# PCB_project_2020-06-05_12-44-14.net
KiCad netlist of a schematic drawn in EasyEDA
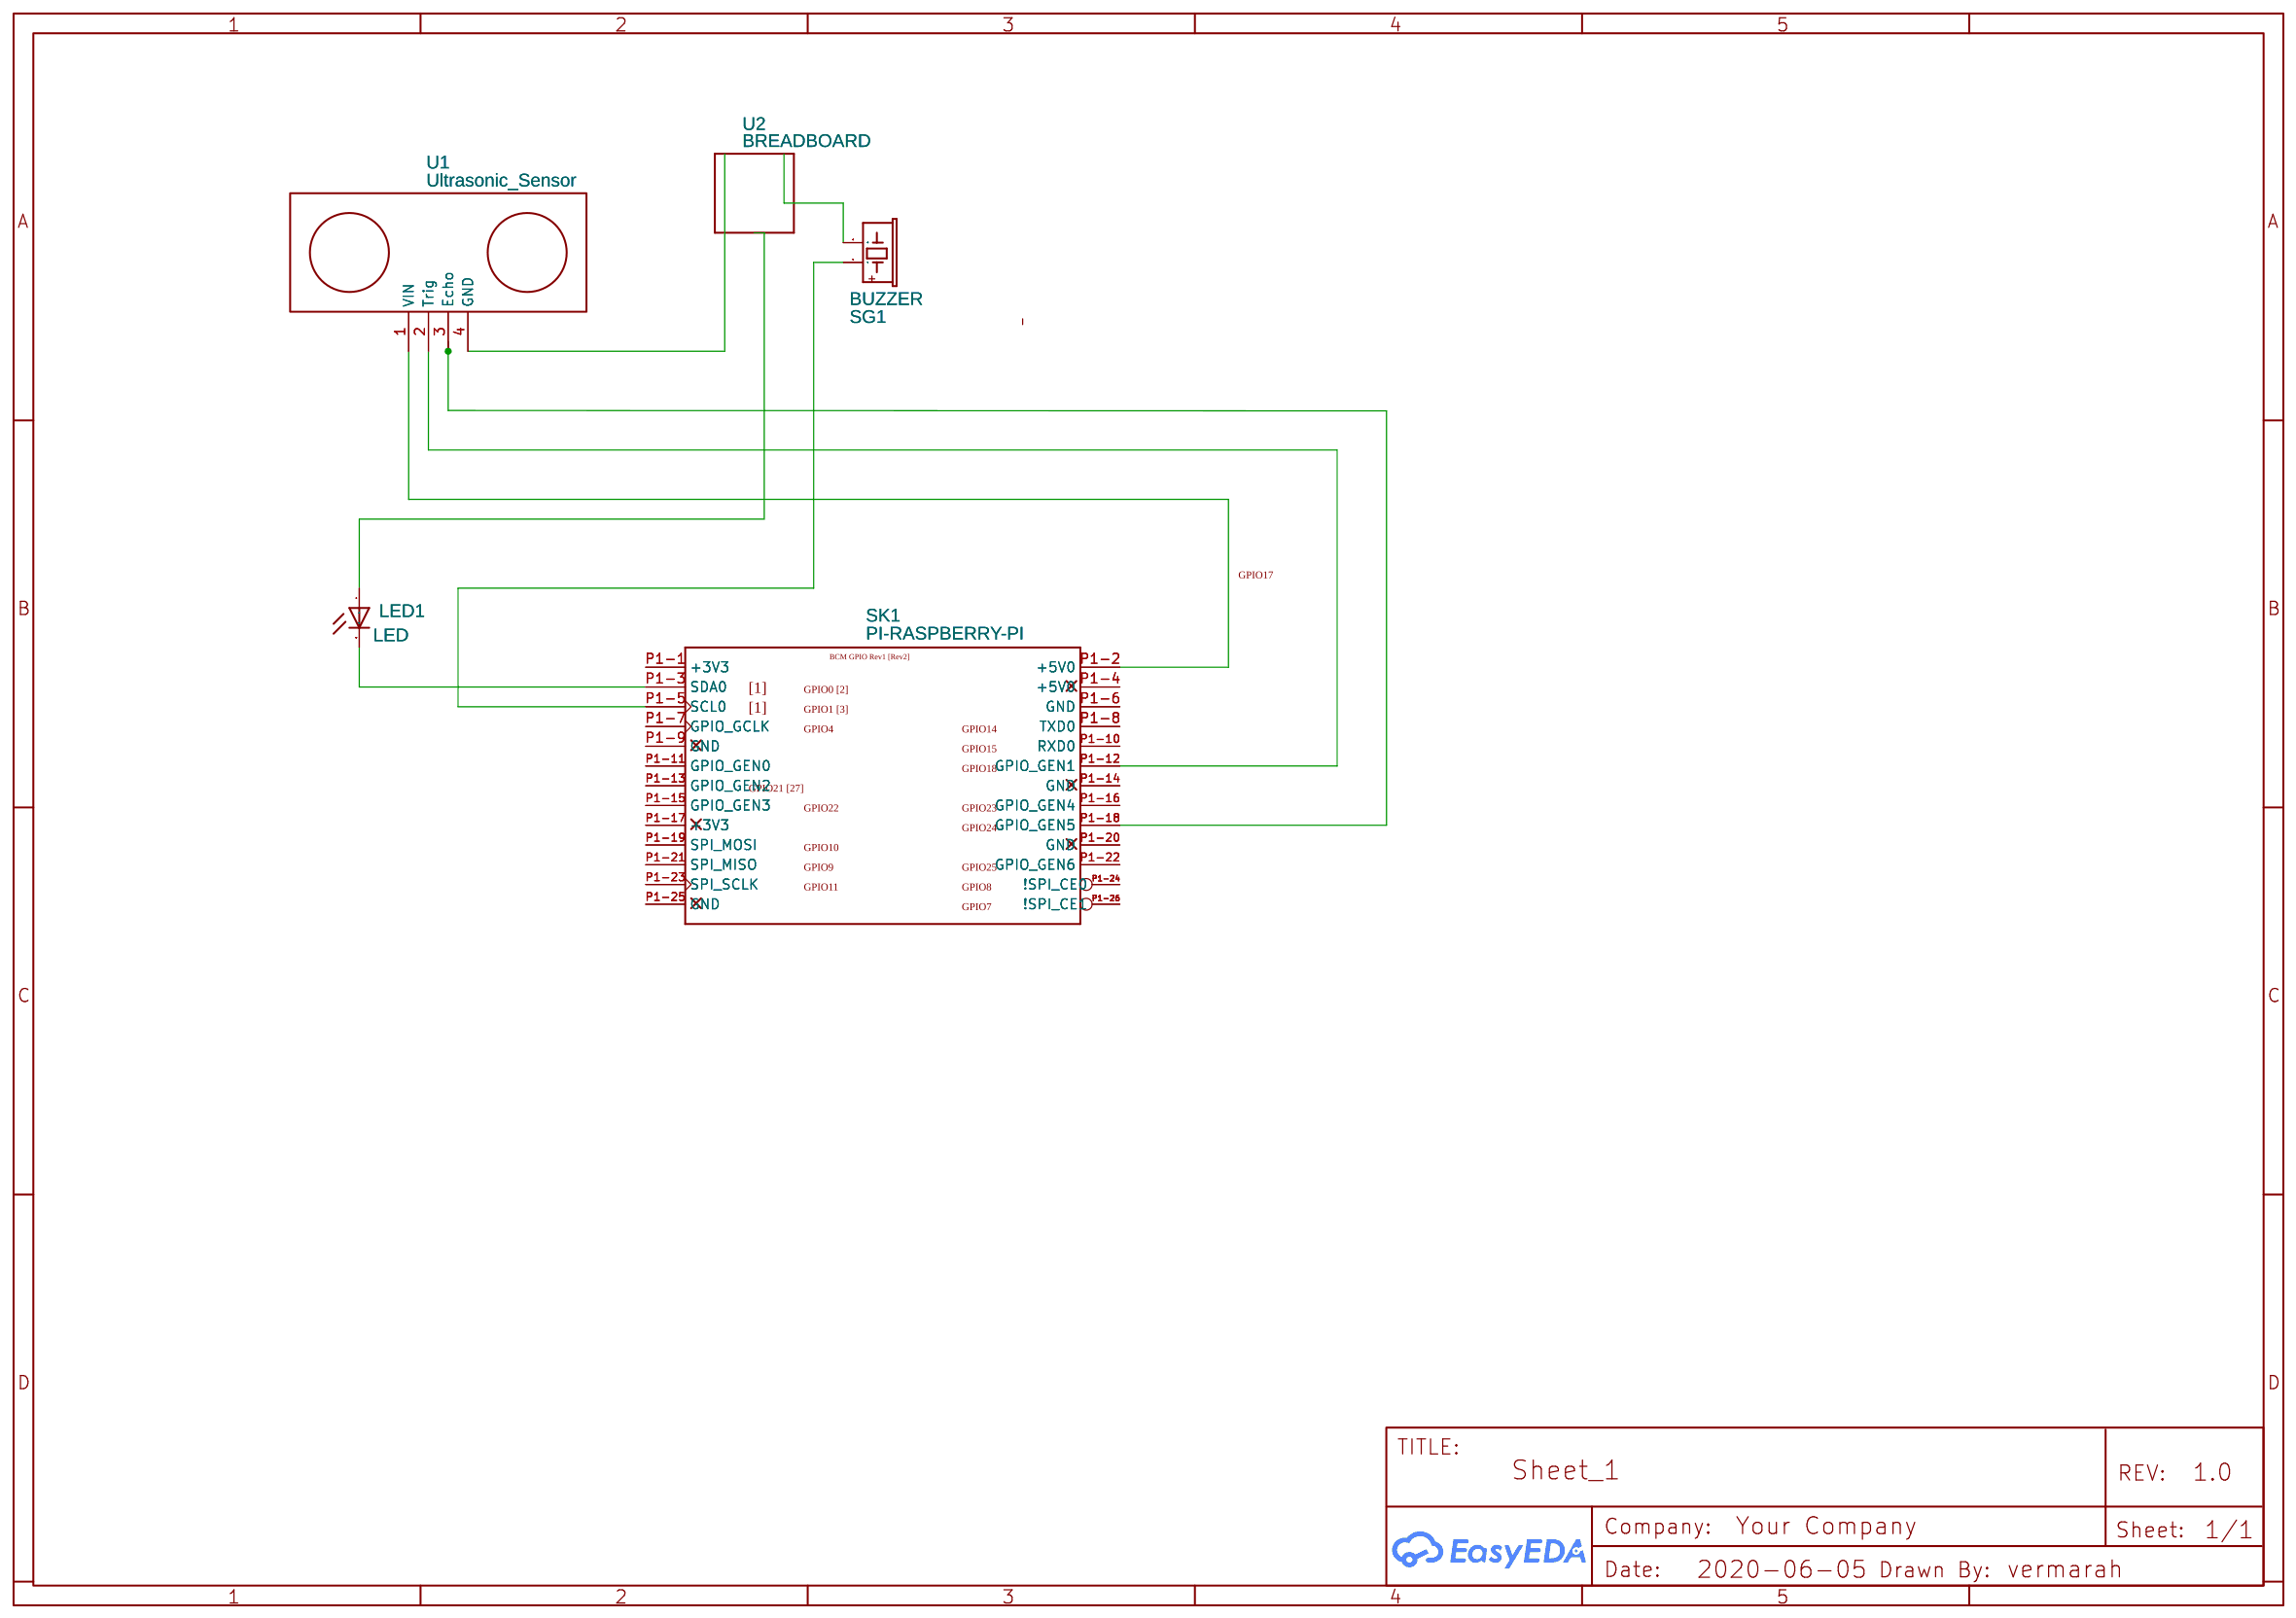
[diagram p0: schematic sheet]

(export (version "E")
  (design (tool "Eeschema 10.0.6"))
  (components
    (comp (ref "LED1") (value "LED") (libsource (lib "") (part "LED")))
    (comp (ref "SG1") (value "BUZZER") (libsource (lib "") (part "BUZZER")))
    (comp (ref "SK1") (value "PI-RASPBERRY-PI") (libsource (lib "") (part "PI-RASPBERRY-PI")))
    (comp (ref "U1")
      (value "Ultrasonic_Sensor")
      (fields (field (name "BOM_Manufacturer Part") "New SchematicLib"))
      (libsource (lib "") (part "Ultrasonic_Sensor"))
    )
    (comp (ref "U2") (value "BREADBOARD") (libsource (lib "") (part "BREADBOARD")))
  )
  (nets
    (net (code "1") (name "Net-(SK1-GPIO_GEN1)") (class "Default")
      (node (ref "SK1") (pin "P1-12") (pinfunction "GPIO_GEN1_P1-12") (pintype "unspecified"))
      (node (ref "U1") (pin "2") (pinfunction "Trig_2") (pintype "unspecified"))
    )
    (net (code "2") (name "Net-(SK1-GPIO_GEN5)") (class "Default")
      (node (ref "SK1") (pin "P1-18") (pinfunction "GPIO_GEN5_P1-18") (pintype "unspecified"))
      (node (ref "U1") (pin "3") (pinfunction "Echo_3") (pintype "unspecified"))
    )
    (net (code "3") (name "Net-(SK1-SCL0)") (class "Default")
      (node (ref "SG1") (pin "1") (pinfunction "1_1") (pintype "unspecified"))
      (node (ref "SK1") (pin "P1-5") (pinfunction "SCL0_P1-5") (pintype "unspecified"))
    )
    (net (code "4") (name "Net-(SK1-SDA0)") (class "Default")
      (node (ref "LED1") (pin "C") (pinfunction "C_C") (pintype "unspecified"))
      (node (ref "SK1") (pin "P1-3") (pinfunction "SDA0_P1-3") (pintype "unspecified"))
    )
    (net (code "5") (name "Net-(U1-VIN)") (class "Default")
      (node (ref "SK1") (pin "P1-2") (pinfunction "+5V0_P1-2") (pintype "passive"))
      (node (ref "U1") (pin "1") (pinfunction "VIN_1") (pintype "unspecified"))
    )
    (net (code "6") (name "unconnected-(LED1-PadA)") (class "Default")
      (node (ref "LED1") (pin "A") (pinfunction "A_A") (pintype "unspecified"))
    )
    (net (code "7") (name "unconnected-(SG1-Pad2)") (class "Default")
      (node (ref "SG1") (pin "2") (pinfunction "2_2") (pintype "unspecified"))
    )
    (net (code "8") (name "unconnected-(SK1-!SPI_CE0-PadP1-24)") (class "Default")
      (node (ref "SK1") (pin "P1-24") (pinfunction "!SPI_CE0_P1-24") (pintype "unspecified"))
    )
    (net (code "9") (name "unconnected-(SK1-!SPI_CE1-PadP1-26)") (class "Default")
      (node (ref "SK1") (pin "P1-26") (pinfunction "!SPI_CE1_P1-26") (pintype "unspecified"))
    )
    (net (code "10") (name "unconnected-(SK1-+3V3-PadP1-1)") (class "Default")
      (node (ref "SK1") (pin "P1-1") (pinfunction "+3V3_P1-1") (pintype "passive"))
    )
    (net (code "11") (name "unconnected-(SK1-+3V3-PadP1-17)") (class "Default")
      (node (ref "SK1") (pin "P1-17") (pinfunction "+3V3_P1-17") (pintype "unspecified"))
    )
    (net (code "12") (name "unconnected-(SK1-+5V0-PadP1-4)") (class "Default")
      (node (ref "SK1") (pin "P1-4") (pinfunction "+5V0_P1-4") (pintype "unspecified"))
    )
    (net (code "13") (name "unconnected-(SK1-GND-PadP1-6)") (class "Default")
      (node (ref "SK1") (pin "P1-6") (pinfunction "GND_P1-6") (pintype "passive"))
    )
    (net (code "14") (name "unconnected-(SK1-GND-PadP1-9)") (class "Default")
      (node (ref "SK1") (pin "P1-9") (pinfunction "GND_P1-9") (pintype "unspecified"))
    )
    (net (code "15") (name "unconnected-(SK1-GND-PadP1-14)") (class "Default")
      (node (ref "SK1") (pin "P1-14") (pinfunction "GND_P1-14") (pintype "unspecified"))
    )
    (net (code "16") (name "unconnected-(SK1-GND-PadP1-20)") (class "Default")
      (node (ref "SK1") (pin "P1-20") (pinfunction "GND_P1-20") (pintype "unspecified"))
    )
    (net (code "17") (name "unconnected-(SK1-GND-PadP1-25)") (class "Default")
      (node (ref "SK1") (pin "P1-25") (pinfunction "GND_P1-25") (pintype "unspecified"))
    )
    (net (code "18") (name "unconnected-(SK1-GPIO_GCLK-PadP1-7)") (class "Default")
      (node (ref "SK1") (pin "P1-7") (pinfunction "GPIO_GCLK_P1-7") (pintype "unspecified"))
    )
    (net (code "19") (name "unconnected-(SK1-GPIO_GEN0-PadP1-11)") (class "Default")
      (node (ref "SK1") (pin "P1-11") (pinfunction "GPIO_GEN0_P1-11") (pintype "unspecified"))
    )
    (net (code "20") (name "unconnected-(SK1-GPIO_GEN2-PadP1-13)") (class "Default")
      (node (ref "SK1") (pin "P1-13") (pinfunction "GPIO_GEN2_P1-13") (pintype "unspecified"))
    )
    (net (code "21") (name "unconnected-(SK1-GPIO_GEN3-PadP1-15)") (class "Default")
      (node (ref "SK1") (pin "P1-15") (pinfunction "GPIO_GEN3_P1-15") (pintype "unspecified"))
    )
    (net (code "22") (name "unconnected-(SK1-GPIO_GEN4-PadP1-16)") (class "Default")
      (node (ref "SK1") (pin "P1-16") (pinfunction "GPIO_GEN4_P1-16") (pintype "unspecified"))
    )
    (net (code "23") (name "unconnected-(SK1-GPIO_GEN6-PadP1-22)") (class "Default")
      (node (ref "SK1") (pin "P1-22") (pinfunction "GPIO_GEN6_P1-22") (pintype "unspecified"))
    )
    (net (code "24") (name "unconnected-(SK1-RXD0-PadP1-10)") (class "Default")
      (node (ref "SK1") (pin "P1-10") (pinfunction "RXD0_P1-10") (pintype "unspecified"))
    )
    (net (code "25") (name "unconnected-(SK1-SPI_MISO-PadP1-21)") (class "Default")
      (node (ref "SK1") (pin "P1-21") (pinfunction "SPI_MISO_P1-21") (pintype "unspecified"))
    )
    (net (code "26") (name "unconnected-(SK1-SPI_MOSI-PadP1-19)") (class "Default")
      (node (ref "SK1") (pin "P1-19") (pinfunction "SPI_MOSI_P1-19") (pintype "unspecified"))
    )
    (net (code "27") (name "unconnected-(SK1-SPI_SCLK-PadP1-23)") (class "Default")
      (node (ref "SK1") (pin "P1-23") (pinfunction "SPI_SCLK_P1-23") (pintype "unspecified"))
    )
    (net (code "28") (name "unconnected-(SK1-TXD0-PadP1-8)") (class "Default")
      (node (ref "SK1") (pin "P1-8") (pinfunction "TXD0_P1-8") (pintype "unspecified"))
    )
    (net (code "29") (name "unconnected-(U1-GND-Pad4)") (class "Default")
      (node (ref "U1") (pin "4") (pinfunction "GND_4") (pintype "unspecified"))
    )
  )
)
